# 3_downstream_con.net
KiCad netlist of a schematic drawn in Altium Designer
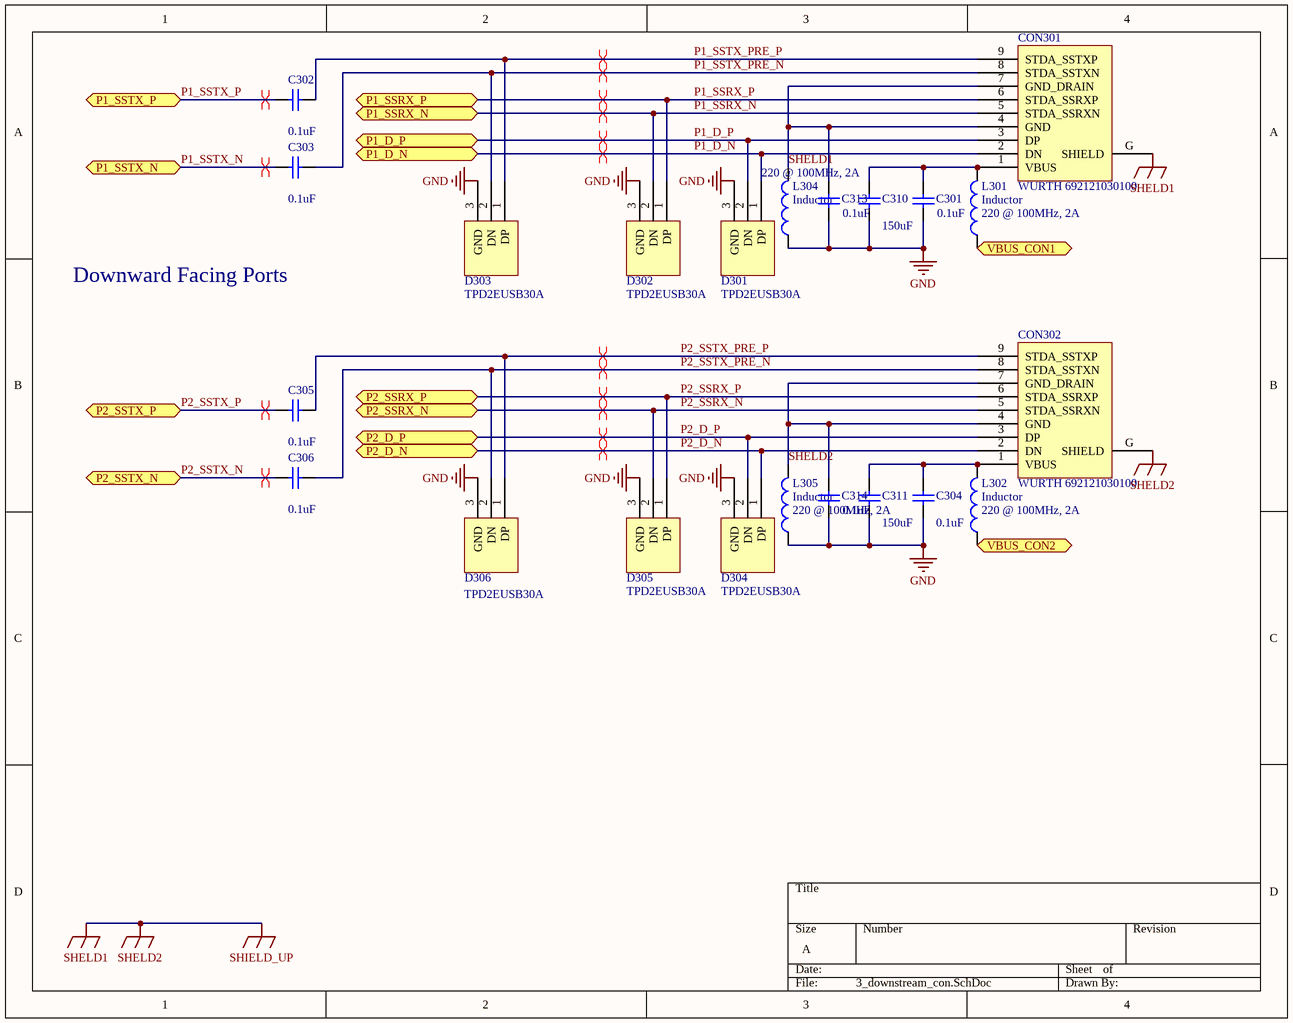
[diagram p0: 3_downstream_con.SchDoc]

(export (version "E")
  (design (tool "Eeschema 10.0.6"))
  (components
    (comp (ref "C301")
      (value "0.1uF")
      (footprint "C0603[1608]")
      (description "Capacitor")
      (fields (field (name "MFG") "KEMET"))
      (libsource (lib "Miscellaneous Devices") (part "Cap"))
    )
    (comp (ref "C302")
      (value "0.1uF")
      (footprint "C0402[1005]")
      (description "Capacitor")
      (fields (field (name "MFG") "KEMET"))
      (libsource (lib "Miscellaneous Devices") (part "Cap"))
    )
    (comp (ref "C303")
      (value "0.1uF")
      (footprint "C0402[1005]")
      (description "Capacitor")
      (fields (field (name "MFG") "KEMET"))
      (libsource (lib "Miscellaneous Devices") (part "Cap"))
    )
    (comp (ref "C304")
      (value "0.1uF")
      (footprint "C0603[1608]")
      (description "Capacitor")
      (fields (field (name "MFG") "KEMET"))
      (libsource (lib "Miscellaneous Devices") (part "Cap"))
    )
    (comp (ref "C305")
      (value "0.1uF")
      (footprint "C0402[1005]")
      (description "Capacitor")
      (fields (field (name "MFG") "KEMET"))
      (libsource (lib "Miscellaneous Devices") (part "Cap"))
    )
    (comp (ref "C306")
      (value "0.1uF")
      (footprint "C0402[1005]")
      (description "Capacitor")
      (fields (field (name "MFG") "KEMET"))
      (libsource (lib "Miscellaneous Devices") (part "Cap"))
    )
    (comp (ref "C310")
      (value "150uF")
      (footprint "C_9G_9H")
      (description "Capacitor")
      (fields (field (name "MFG") "United Chemi-Con"))
      (libsource (lib "Miscellaneous Devices") (part "Cap"))
    )
    (comp (ref "C311")
      (value "150uF")
      (footprint "C_9G_9H")
      (description "Capacitor")
      (fields (field (name "MFG") "United Chemi-Con"))
      (libsource (lib "Miscellaneous Devices") (part "Cap"))
    )
    (comp (ref "C313")
      (value "0.1uF")
      (footprint "C0603[1608]")
      (description "Capacitor")
      (fields (field (name "MFG") "KEMET"))
      (libsource (lib "Miscellaneous Devices") (part "Cap"))
    )
    (comp (ref "C314")
      (value "0.1uF")
      (footprint "C0603[1608]")
      (description "Capacitor")
      (fields (field (name "MFG") "KEMET"))
      (libsource (lib "Miscellaneous Devices") (part "Cap"))
    )
    (comp (ref "CON301")
      (value "WURTH 692121030100")
      (footprint "WURTH 692122030100")
      (fields (field (name "MFG") "Wurth Electronics Inc"))
      (libsource (lib "lib") (part "WURTH 692121030100"))
    )
    (comp (ref "CON302")
      (value "WURTH 692121030100")
      (footprint "WURTH 692122030100")
      (fields (field (name "MFG") "Wurth Electronics Inc"))
      (libsource (lib "lib") (part "WURTH 692121030100"))
    )
    (comp (ref "D301")
      (value "TPD2EUSB30A")
      (footprint "TPD2EUSB30A")
      (fields (field (name "MFG") "Texas Instruments"))
      (libsource (lib "lib") (part "TPD2EUSB30A"))
    )
    (comp (ref "D302")
      (value "TPD2EUSB30A")
      (footprint "TPD2EUSB30A")
      (fields (field (name "MFG") "Texas Instruments"))
      (libsource (lib "lib") (part "TPD2EUSB30A"))
    )
    (comp (ref "D303")
      (value "TPD2EUSB30A")
      (footprint "TPD2EUSB30A")
      (fields (field (name "MFG") "Texas Instruments"))
      (libsource (lib "lib") (part "TPD2EUSB30A"))
    )
    (comp (ref "D304")
      (value "TPD2EUSB30A")
      (footprint "TPD2EUSB30A")
      (fields (field (name "MFG") "Texas Instruments"))
      (libsource (lib "lib") (part "TPD2EUSB30A"))
    )
    (comp (ref "D305")
      (value "TPD2EUSB30A")
      (footprint "TPD2EUSB30A")
      (fields (field (name "MFG") "Texas Instruments"))
      (libsource (lib "lib") (part "TPD2EUSB30A"))
    )
    (comp (ref "D306")
      (value "TPD2EUSB30A")
      (footprint "TPD2EUSB30A")
      (fields (field (name "MFG") "Texas Instruments"))
      (libsource (lib "lib") (part "TPD2EUSB30A"))
    )
    (comp (ref "L301")
      (value "Inductor")
      (footprint "L0603[1608]")
      (fields
        (field (name "ALTIUM_VALUE") "220 @ 100MHz, 2A")
        (field (name "MFG") "Murata Electronics North America")
      )
      (libsource (lib "Miscellaneous Devices") (part "Inductor"))
    )
    (comp (ref "L302")
      (value "Inductor")
      (footprint "L0603[1608]")
      (fields
        (field (name "ALTIUM_VALUE") "220 @ 100MHz, 2A")
        (field (name "MFG") "Murata Electronics North America")
      )
      (libsource (lib "Miscellaneous Devices") (part "Inductor"))
    )
    (comp (ref "L304")
      (value "Inductor")
      (footprint "L0603[1608]")
      (fields
        (field (name "ALTIUM_VALUE") "220 @ 100MHz, 2A")
        (field (name "MFG") "Murata Electronics North America")
      )
      (libsource (lib "Miscellaneous Devices") (part "Inductor"))
    )
    (comp (ref "L305")
      (value "Inductor")
      (footprint "L0603[1608]")
      (fields
        (field (name "ALTIUM_VALUE") "220 @ 100MHz, 2A")
        (field (name "MFG") "Murata Electronics North America")
      )
      (libsource (lib "Miscellaneous Devices") (part "Inductor"))
    )
  )
  (nets
    (net (code "1") (name "/P1_D_N") (class "Default")
      (node (ref "CON301") (pin "2") (pinfunction "DN_2") (pintype "passive"))
      (node (ref "D301") (pin "1") (pinfunction "DP_1") (pintype "passive"))
    )
    (net (code "2") (name "/P1_D_P") (class "Default")
      (node (ref "CON301") (pin "3") (pinfunction "DP_3") (pintype "passive"))
      (node (ref "D301") (pin "2") (pinfunction "DN_2") (pintype "passive"))
    )
    (net (code "3") (name "/P1_SSRX_N") (class "Default")
      (node (ref "CON301") (pin "5") (pinfunction "STDA_SSRXN_5") (pintype "passive"))
      (node (ref "D302") (pin "2") (pinfunction "DN_2") (pintype "passive"))
    )
    (net (code "4") (name "/P1_SSRX_P") (class "Default")
      (node (ref "CON301") (pin "6") (pinfunction "STDA_SSRXP_6") (pintype "passive"))
      (node (ref "D302") (pin "1") (pinfunction "DP_1") (pintype "passive"))
    )
    (net (code "5") (name "/P1_SSTX_N") (class "Default")
      (node (ref "C303") (pin "2") (pinfunction "2_2") (pintype "passive"))
    )
    (net (code "6") (name "/P1_SSTX_P") (class "Default")
      (node (ref "C302") (pin "2") (pinfunction "2_2") (pintype "passive"))
    )
    (net (code "7") (name "/P1_SSTX_PRE_N") (class "Default")
      (node (ref "C303") (pin "1") (pinfunction "1_1") (pintype "passive"))
      (node (ref "CON301") (pin "8") (pinfunction "STDA_SSTXN_8") (pintype "passive"))
      (node (ref "D303") (pin "2") (pinfunction "DN_2") (pintype "passive"))
    )
    (net (code "8") (name "/P1_SSTX_PRE_P") (class "Default")
      (node (ref "C302") (pin "1") (pinfunction "1_1") (pintype "passive"))
      (node (ref "CON301") (pin "9") (pinfunction "STDA_SSTXP_9") (pintype "passive"))
      (node (ref "D303") (pin "1") (pinfunction "DP_1") (pintype "passive"))
    )
    (net (code "9") (name "/P2_D_N") (class "Default")
      (node (ref "CON302") (pin "2") (pinfunction "DN_2") (pintype "passive"))
      (node (ref "D304") (pin "1") (pinfunction "DP_1") (pintype "passive"))
    )
    (net (code "10") (name "/P2_D_P") (class "Default")
      (node (ref "CON302") (pin "3") (pinfunction "DP_3") (pintype "passive"))
      (node (ref "D304") (pin "2") (pinfunction "DN_2") (pintype "passive"))
    )
    (net (code "11") (name "/P2_SSRX_N") (class "Default")
      (node (ref "CON302") (pin "5") (pinfunction "STDA_SSRXN_5") (pintype "passive"))
      (node (ref "D305") (pin "2") (pinfunction "DN_2") (pintype "passive"))
    )
    (net (code "12") (name "/P2_SSRX_P") (class "Default")
      (node (ref "CON302") (pin "6") (pinfunction "STDA_SSRXP_6") (pintype "passive"))
      (node (ref "D305") (pin "1") (pinfunction "DP_1") (pintype "passive"))
    )
    (net (code "13") (name "/P2_SSTX_N") (class "Default")
      (node (ref "C306") (pin "1") (pinfunction "1_1") (pintype "passive"))
    )
    (net (code "14") (name "/P2_SSTX_P") (class "Default")
      (node (ref "C305") (pin "1") (pinfunction "1_1") (pintype "passive"))
    )
    (net (code "15") (name "/P2_SSTX_PRE_N") (class "Default")
      (node (ref "C306") (pin "2") (pinfunction "2_2") (pintype "passive"))
      (node (ref "CON302") (pin "8") (pinfunction "STDA_SSTXN_8") (pintype "passive"))
      (node (ref "D306") (pin "2") (pinfunction "DN_2") (pintype "passive"))
    )
    (net (code "16") (name "/P2_SSTX_PRE_P") (class "Default")
      (node (ref "C305") (pin "2") (pinfunction "2_2") (pintype "passive"))
      (node (ref "CON302") (pin "9") (pinfunction "STDA_SSTXP_9") (pintype "passive"))
      (node (ref "D306") (pin "1") (pinfunction "DP_1") (pintype "passive"))
    )
    (net (code "17") (name "/VBUS_CON1") (class "Default")
      (node (ref "L301") (pin "1") (pinfunction "1_1") (pintype "passive"))
    )
    (net (code "18") (name "/VBUS_CON2") (class "Default")
      (node (ref "L302") (pin "1") (pinfunction "1_1") (pintype "passive"))
    )
    (net (code "19") (name "GND") (class "Default")
      (node (ref "C301") (pin "1") (pinfunction "1_1") (pintype "passive"))
      (node (ref "C304") (pin "1") (pinfunction "1_1") (pintype "passive"))
      (node (ref "C310") (pin "1") (pinfunction "1_1") (pintype "passive"))
      (node (ref "C311") (pin "1") (pinfunction "1_1") (pintype "passive"))
      (node (ref "C313") (pin "1") (pinfunction "1_1") (pintype "passive"))
      (node (ref "C314") (pin "1") (pinfunction "1_1") (pintype "passive"))
      (node (ref "D301") (pin "3") (pinfunction "GND_3") (pintype "passive"))
      (node (ref "D302") (pin "3") (pinfunction "GND_3") (pintype "passive"))
      (node (ref "D303") (pin "3") (pinfunction "GND_3") (pintype "passive"))
      (node (ref "D304") (pin "3") (pinfunction "GND_3") (pintype "passive"))
      (node (ref "D305") (pin "3") (pinfunction "GND_3") (pintype "passive"))
      (node (ref "D306") (pin "3") (pinfunction "GND_3") (pintype "passive"))
      (node (ref "L304") (pin "1") (pinfunction "1_1") (pintype "passive"))
      (node (ref "L305") (pin "1") (pinfunction "1_1") (pintype "passive"))
    )
    (net (code "20") (name "Net-(CON301-VBUS)") (class "Default")
      (node (ref "C301") (pin "2") (pinfunction "2_2") (pintype "passive"))
      (node (ref "C310") (pin "2") (pinfunction "2_2") (pintype "passive"))
      (node (ref "CON301") (pin "1") (pinfunction "VBUS_1") (pintype "passive"))
      (node (ref "L301") (pin "2") (pinfunction "2_2") (pintype "passive"))
    )
    (net (code "21") (name "Net-(CON302-VBUS)") (class "Default")
      (node (ref "C304") (pin "2") (pinfunction "2_2") (pintype "passive"))
      (node (ref "C311") (pin "2") (pinfunction "2_2") (pintype "passive"))
      (node (ref "CON302") (pin "1") (pinfunction "VBUS_1") (pintype "passive"))
      (node (ref "L302") (pin "2") (pinfunction "2_2") (pintype "passive"))
    )
    (net (code "22") (name "SHELD1") (class "Default")
      (node (ref "C313") (pin "2") (pinfunction "2_2") (pintype "passive"))
      (node (ref "C314") (pin "2") (pinfunction "2_2") (pintype "passive"))
      (node (ref "CON301") (pin "4") (pinfunction "GND_4") (pintype "passive"))
      (node (ref "CON301") (pin "7") (pinfunction "GND_DRAIN_7") (pintype "passive"))
      (node (ref "CON301") (pin "G") (pinfunction "SHIELD_G") (pintype "passive"))
      (node (ref "CON302") (pin "4") (pinfunction "GND_4") (pintype "passive"))
      (node (ref "CON302") (pin "7") (pinfunction "GND_DRAIN_7") (pintype "passive"))
      (node (ref "CON302") (pin "G") (pinfunction "SHIELD_G") (pintype "passive"))
      (node (ref "L304") (pin "2") (pinfunction "2_2") (pintype "passive"))
      (node (ref "L305") (pin "2") (pinfunction "2_2") (pintype "passive"))
    )
  )
)
